# visitor_counter.net
KiCad netlist of a schematic drawn in EAGLE
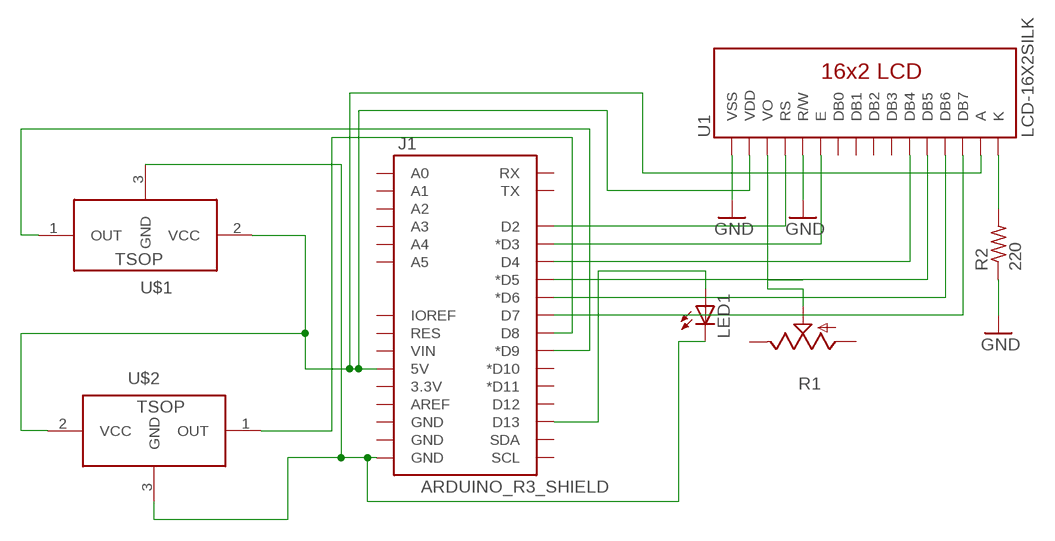
[diagram p0: schematic, sheet 1]

(export (version "E")
  (design (tool "Eeschema 10.0.6"))
  (components
    (comp (ref "J1")
      (value "ARDUINO_R3_SHIELD")
      (footprint "eagle-import:UNO_R3_SHIELD")
      (libsource (lib "eagle-import") (part "ARDUINO_R3_SHIELD"))
    )
    (comp (ref "LED1")
      (value "LED5MM")
      (footprint "eagle-import:LED5MM")
      (libsource (lib "eagle-import") (part "LED5MM"))
    )
    (comp (ref "R1")
      (value "TRIM_US-CIP20C-4MM")
      (footprint "eagle-import:CIP20C-4MM")
      (libsource (lib "eagle-import") (part "TRIM_US-CIP20C-4MM"))
    )
    (comp (ref "R2")
      (value "220")
      (footprint "eagle-import:0204_7")
      (libsource (lib "eagle-import") (part "R-US_0204/7"))
    )
    (comp (ref "U$1")
      (value "TSOP34X")
      (footprint "eagle-import:TSOP3XXX")
      (libsource (lib "eagle-import") (part "TSOP34X"))
    )
    (comp (ref "U$2")
      (value "TSOP34X")
      (footprint "eagle-import:TSOP3XXX")
      (libsource (lib "eagle-import") (part "TSOP34X"))
    )
    (comp (ref "U1")
      (value "LCD-16X2SILK")
      (footprint "eagle-import:LCD-16X2")
      (libsource (lib "eagle-import") (part "LCD-16X2SILK"))
    )
  )
  (nets
    (net (code "1") (name "GND") (class "Default")
      (node (ref "R2") (pin "1") (pinfunction "1_1") (pintype "passive"))
      (node (ref "U1") (pin "1") (pinfunction "VSS_1") (pintype "power_in"))
      (node (ref "U1") (pin "5") (pinfunction "R/W_5") (pintype "input"))
    )
    (net (code "2") (name "Net-(J1-*D3)") (class "Default")
      (node (ref "J1") (pin "D3") (pinfunction "*D3_D3") (pintype "bidirectional"))
      (node (ref "U1") (pin "6") (pinfunction "E_6") (pintype "input"))
    )
    (net (code "3") (name "Net-(J1-*D5)") (class "Default")
      (node (ref "J1") (pin "D5") (pinfunction "*D5_D5") (pintype "bidirectional"))
      (node (ref "U1") (pin "12") (pinfunction "DB5_12") (pintype "bidirectional"))
    )
    (net (code "4") (name "Net-(J1-*D6)") (class "Default")
      (node (ref "J1") (pin "D6") (pinfunction "*D6_D6") (pintype "bidirectional"))
      (node (ref "U1") (pin "13") (pinfunction "DB6_13") (pintype "bidirectional"))
    )
    (net (code "5") (name "Net-(J1-*D9)") (class "Default")
      (node (ref "J1") (pin "D9") (pinfunction "*D9_D9") (pintype "bidirectional"))
      (node (ref "U$1") (pin "1") (pinfunction "OUT_1") (pintype "output"))
    )
    (net (code "6") (name "Net-(J1-PadD13)") (class "Default")
      (node (ref "J1") (pin "D13") (pinfunction "D13_D13") (pintype "bidirectional"))
      (node (ref "LED1") (pin "A") (pinfunction "A_A") (pintype "passive"))
    )
    (net (code "7") (name "Net-(LED1-C)") (class "Default")
      (node (ref "J1") (pin "GND@0") (pinfunction "GND_GND@0") (pintype "bidirectional"))
      (node (ref "LED1") (pin "K") (pinfunction "C_K") (pintype "passive"))
      (node (ref "U$1") (pin "3") (pinfunction "GND_3") (pintype "power_in"))
      (node (ref "U$2") (pin "3") (pinfunction "GND_3") (pintype "power_in"))
    )
    (net (code "8") (name "Net-(U$1-VCC)") (class "Default")
      (node (ref "J1") (pin "5V") (pinfunction "5V_5V") (pintype "bidirectional"))
      (node (ref "U$1") (pin "2") (pinfunction "VCC_2") (pintype "power_in"))
      (node (ref "U$2") (pin "2") (pinfunction "VCC_2") (pintype "power_in"))
      (node (ref "U1") (pin "15") (pinfunction "A_15") (pintype "power_in"))
      (node (ref "U1") (pin "2") (pinfunction "VDD_2") (pintype "power_in"))
    )
    (net (code "9") (name "Net-(U$2-OUT)") (class "Default")
      (node (ref "J1") (pin "D8") (pinfunction "D8_D8") (pintype "bidirectional"))
      (node (ref "U$2") (pin "1") (pinfunction "OUT_1") (pintype "output"))
    )
    (net (code "10") (name "Net-(U1-DB4)") (class "Default")
      (node (ref "J1") (pin "D4") (pinfunction "D4_D4") (pintype "bidirectional"))
      (node (ref "U1") (pin "11") (pinfunction "DB4_11") (pintype "bidirectional"))
    )
    (net (code "11") (name "Net-(U1-DB7)") (class "Default")
      (node (ref "J1") (pin "D7") (pinfunction "D7_D7") (pintype "bidirectional"))
      (node (ref "U1") (pin "14") (pinfunction "DB7_14") (pintype "bidirectional"))
    )
    (net (code "12") (name "Net-(U1-K)") (class "Default")
      (node (ref "R2") (pin "2") (pinfunction "2_2") (pintype "passive"))
      (node (ref "U1") (pin "16") (pinfunction "K_16") (pintype "power_in"))
    )
    (net (code "13") (name "Net-(U1-RS)") (class "Default")
      (node (ref "J1") (pin "D2") (pinfunction "D2_D2") (pintype "bidirectional"))
      (node (ref "U1") (pin "4") (pinfunction "RS_4") (pintype "input"))
    )
    (net (code "14") (name "Net-(U1-VO)") (class "Default")
      (node (ref "R1") (pin "S") (pinfunction "S_S") (pintype "passive"))
      (node (ref "U1") (pin "3") (pinfunction "VO_3") (pintype "bidirectional"))
    )
    (net (code "15") (name "unconnected-(J1-*D10-PadD10)") (class "Default")
      (node (ref "J1") (pin "D10") (pinfunction "*D10_D10") (pintype "bidirectional"))
    )
    (net (code "16") (name "unconnected-(J1-*D11-PadD11)") (class "Default")
      (node (ref "J1") (pin "D11") (pinfunction "*D11_D11") (pintype "bidirectional"))
    )
    (net (code "17") (name "unconnected-(J1-GND-PadGND@1)") (class "Default")
      (node (ref "J1") (pin "GND@1") (pinfunction "GND_GND@1") (pintype "bidirectional"))
    )
    (net (code "18") (name "unconnected-(J1-GND-PadGND@2)") (class "Default")
      (node (ref "J1") (pin "GND@2") (pinfunction "GND_GND@2") (pintype "bidirectional"))
    )
    (net (code "19") (name "unconnected-(J1-Pad3.3V)") (class "Default")
      (node (ref "J1") (pin "3.3V") (pinfunction "3.3V_3.3V") (pintype "bidirectional"))
    )
    (net (code "20") (name "unconnected-(J1-PadA0)") (class "Default")
      (node (ref "J1") (pin "A0") (pinfunction "A0_A0") (pintype "bidirectional"))
    )
    (net (code "21") (name "unconnected-(J1-PadA1)") (class "Default")
      (node (ref "J1") (pin "A1") (pinfunction "A1_A1") (pintype "bidirectional"))
    )
    (net (code "22") (name "unconnected-(J1-PadA2)") (class "Default")
      (node (ref "J1") (pin "A2") (pinfunction "A2_A2") (pintype "bidirectional"))
    )
    (net (code "23") (name "unconnected-(J1-PadA3)") (class "Default")
      (node (ref "J1") (pin "A3") (pinfunction "A3_A3") (pintype "bidirectional"))
    )
    (net (code "24") (name "unconnected-(J1-PadA4)") (class "Default")
      (node (ref "J1") (pin "A4") (pinfunction "A4_A4") (pintype "bidirectional"))
    )
    (net (code "25") (name "unconnected-(J1-PadA5)") (class "Default")
      (node (ref "J1") (pin "A5") (pinfunction "A5_A5") (pintype "bidirectional"))
    )
    (net (code "26") (name "unconnected-(J1-PadAREF)") (class "Default")
      (node (ref "J1") (pin "AREF") (pinfunction "AREF_AREF") (pintype "bidirectional"))
    )
    (net (code "27") (name "unconnected-(J1-PadD12)") (class "Default")
      (node (ref "J1") (pin "D12") (pinfunction "D12_D12") (pintype "bidirectional"))
    )
    (net (code "28") (name "unconnected-(J1-PadIOREF)") (class "Default")
      (node (ref "J1") (pin "IOREF") (pinfunction "IOREF_IOREF") (pintype "bidirectional"))
    )
    (net (code "29") (name "unconnected-(J1-PadRES)") (class "Default")
      (node (ref "J1") (pin "RES") (pinfunction "RES_RES") (pintype "bidirectional"))
    )
    (net (code "30") (name "unconnected-(J1-PadRX)") (class "Default")
      (node (ref "J1") (pin "RX") (pinfunction "RX_RX") (pintype "bidirectional"))
    )
    (net (code "31") (name "unconnected-(J1-PadSCL)") (class "Default")
      (node (ref "J1") (pin "SCL") (pinfunction "SCL_SCL") (pintype "bidirectional"))
    )
    (net (code "32") (name "unconnected-(J1-PadSDA)") (class "Default")
      (node (ref "J1") (pin "SDA") (pinfunction "SDA_SDA") (pintype "bidirectional"))
    )
    (net (code "33") (name "unconnected-(J1-PadTX)") (class "Default")
      (node (ref "J1") (pin "TX") (pinfunction "TX_TX") (pintype "bidirectional"))
    )
    (net (code "34") (name "unconnected-(J1-PadVIN)") (class "Default")
      (node (ref "J1") (pin "VIN") (pinfunction "VIN_VIN") (pintype "bidirectional"))
    )
    (net (code "35") (name "unconnected-(R1-PadA)") (class "Default")
      (node (ref "R1") (pin "A") (pinfunction "A_A") (pintype "passive"))
    )
    (net (code "36") (name "unconnected-(R1-PadE)") (class "Default")
      (node (ref "R1") (pin "E") (pinfunction "E_E") (pintype "passive"))
    )
    (net (code "37") (name "unconnected-(U1-DB0-Pad7)") (class "Default")
      (node (ref "U1") (pin "7") (pinfunction "DB0_7") (pintype "bidirectional"))
    )
    (net (code "38") (name "unconnected-(U1-DB1-Pad8)") (class "Default")
      (node (ref "U1") (pin "8") (pinfunction "DB1_8") (pintype "bidirectional"))
    )
    (net (code "39") (name "unconnected-(U1-DB2-Pad9)") (class "Default")
      (node (ref "U1") (pin "9") (pinfunction "DB2_9") (pintype "bidirectional"))
    )
    (net (code "40") (name "unconnected-(U1-DB3-Pad10)") (class "Default")
      (node (ref "U1") (pin "10") (pinfunction "DB3_10") (pintype "bidirectional"))
    )
  )
)
